# I2C_DP_Sensor_1.net
KiCad netlist of a schematic drawn in Altium Designer
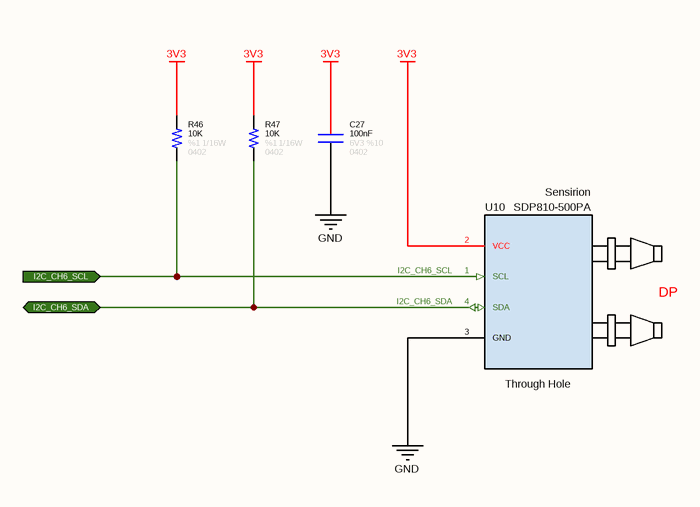
[diagram p0: I2C DP Sensor 1.SchDoc]

(export (version "E")
  (design (tool "Eeschema 10.0.6"))
  (components
    (comp (ref "C27")
      (value "100nF")
      (footprint "CAPACITOR_0402")
      (description "Capacitor - 100nF [0402-6V3] (Ceramic)")
      (fields
        (field (name "MANUFACTURER PART NUMBER") "04026D104KAT4A")
        (field (name "TOLERANCE") "%10")
        (field (name "VOLTAGE") "6V3")
        (field (name "CASE") "0402")
        (field (name "Comment") "Capacitor - 100nF [0402] (Ceramic)")
      )
      (libsource (lib "Akkoyun") (part "Capacitor - 100nF [0402-6V3]"))
    )
    (comp (ref "R46")
      (value "10K")
      (footprint "RESISTOR_0402")
      (description "Thick Film Resistors - SMD 1/16 W 10 KOhm 1%")
      (fields
        (field (name "MANUFACTURER PART NUMBER") "CRCW040210K0FKED")
        (field (name "TOLERANCE") "%1")
        (field (name "CASE") "0402")
        (field (name "POWER") "1/16W")
        (field (name "Comment") "10K - 0402 - %1 - 1/16W")
      )
      (libsource (lib "Akkoyun") (part "Resistor - 10K [0402]"))
    )
    (comp (ref "R47")
      (value "10K")
      (footprint "RESISTOR_0402")
      (description "Thick Film Resistors - SMD 1/16 W 10 KOhm 1%")
      (fields
        (field (name "MANUFACTURER PART NUMBER") "CRCW040210K0FKED")
        (field (name "TOLERANCE") "%1")
        (field (name "CASE") "0402")
        (field (name "POWER") "1/16W")
        (field (name "Comment") "10K - 0402 - %1 - 1/16W")
      )
      (libsource (lib "Akkoyun") (part "Resistor - 10K [0402]"))
    )
    (comp (ref "U10")
      (value "SDP810-500PA")
      (footprint "SDP810-500PA")
      (description "Board Mount Pressure Sensors Tube Connection, I2C , 500Pa")
      (fields
        (field (name "MANUFACTURER NAME") "Sensirion")
        (field (name "MANUFACTURER PART NUMBER") "SDP810-500PA")
        (field (name "CASE") "Through Hole")
      )
      (libsource (lib "Akkoyun") (part "IC - SDP810-500PA"))
    )
  )
  (nets
    (net (code "1") (name "/I2C_CH6_SCL") (class "Default")
      (node (ref "R46") (pin "1") (pinfunction "1_1") (pintype "passive"))
      (node (ref "U10") (pin "1") (pinfunction "SCL_1") (pintype "input"))
    )
    (net (code "2") (name "/I2C_CH6_SDA") (class "Default")
      (node (ref "R47") (pin "1") (pinfunction "1_1") (pintype "passive"))
      (node (ref "U10") (pin "4") (pinfunction "SDA_4") (pintype "bidirectional"))
    )
    (net (code "3") (name "3V3") (class "Default")
      (node (ref "C27") (pin "2") (pinfunction "2_2") (pintype "passive"))
      (node (ref "R46") (pin "2") (pinfunction "2_2") (pintype "passive"))
      (node (ref "R47") (pin "2") (pinfunction "2_2") (pintype "passive"))
      (node (ref "U10") (pin "2") (pinfunction "VCC_2") (pintype "power_in"))
    )
    (net (code "4") (name "GND") (class "Default")
      (node (ref "C27") (pin "1") (pinfunction "1_1") (pintype "passive"))
      (node (ref "U10") (pin "3") (pinfunction "GND_3") (pintype "passive"))
    )
  )
)
